# Sch_Fuente.net
KiCad netlist of a schematic drawn in Altium Designer
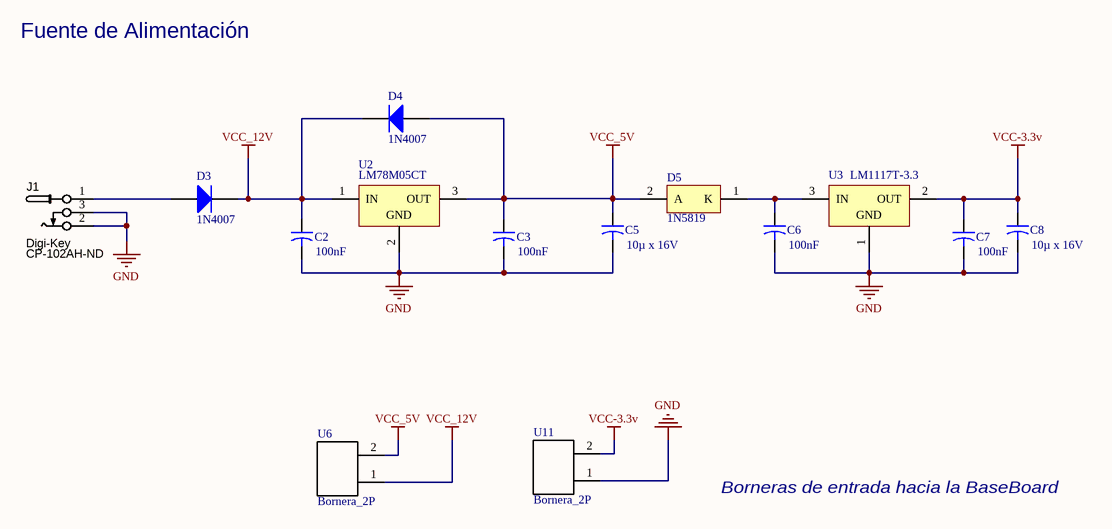
[diagram p0: Sch_Fuente.SchDoc]

(export (version "E")
  (design (tool "Eeschema 10.0.6"))
  (components
    (comp (ref "C2")
      (value "100nF")
      (footprint "CAPR5-4X5")
      (description "Capacitor")
      (fields (field (name "Comment") "Cap2") (field (name "PUBLISHER") "Altium Limited"))
      (libsource (lib "Miscellaneous Devices") (part "Cap2"))
    )
    (comp (ref "C3")
      (value "100nF")
      (footprint "CAPR5-4X5")
      (description "Capacitor")
      (fields (field (name "Comment") "Cap2") (field (name "PUBLISHER") "Altium Limited"))
      (libsource (lib "Miscellaneous Devices") (part "Cap2"))
    )
    (comp (ref "C5")
      (value "10µ x 16V")
      (footprint "CAPR5-4X5")
      (description "Capacitor")
      (fields (field (name "Comment") "Cap2") (field (name "PUBLISHER") "Altium Limited"))
      (libsource (lib "Miscellaneous Devices") (part "Cap2"))
    )
    (comp (ref "C6")
      (value "100nF")
      (footprint "CAPR5-4X5")
      (description "Capacitor")
      (fields (field (name "Comment") "Cap2") (field (name "PUBLISHER") "Altium Limited"))
      (libsource (lib "Miscellaneous Devices") (part "Cap2"))
    )
    (comp (ref "C7")
      (value "100nF")
      (footprint "CAPR5-4X5")
      (description "Capacitor")
      (fields (field (name "Comment") "Cap2") (field (name "PUBLISHER") "Altium Limited"))
      (libsource (lib "Miscellaneous Devices") (part "Cap2"))
    )
    (comp (ref "C8")
      (value "10µ x 16V")
      (footprint "CAPR5-4X5")
      (description "Capacitor")
      (fields (field (name "Comment") "Cap2") (field (name "PUBLISHER") "Altium Limited"))
      (libsource (lib "Miscellaneous Devices") (part "Cap2"))
    )
    (comp (ref "D3")
      (value "1N4007")
      (footprint "DO-41")
      (description "1 Amp General Purpose Rectifier")
      (fields (field (name "PUBLISHER") "Altium Limited"))
      (libsource (lib "Miscellaneous Devices") (part "Diode 1N4007"))
    )
    (comp (ref "D4")
      (value "1N4007")
      (footprint "DO-41")
      (description "1 Amp General Purpose Rectifier")
      (fields (field (name "PUBLISHER") "Altium Limited"))
      (libsource (lib "Miscellaneous Devices") (part "Diode 1N4007"))
    )
    (comp (ref "D5")
      (value "1N5819")
      (footprint "ONSC-AXIAL_LEAD-2-59-10_P")
      (description "Rectifier, 2-Pin Axial_Lead, Pb-Free, Bulk Bag")
      (fields (field (name "MANUFACTURER") "On Semiconductor"))
      (libsource (lib "Altium Content Vault") (part "ONSC-D-K1A2-2_A"))
    )
    (comp (ref "J1")
      (value "CONN_PWR_JACK_2.1x5.5mm")
      (footprint "CONN_PWR_JACK_2.1x5.5mm")
      (description "Power Connector, THT, 2.1mm ID, 5.5mm OD")
      (fields (field (name "SUPPLIER 1") "Digi-Key") (field (name "SUPPLIER PART NUMBER 1") "CP-102AH-ND"))
      (libsource (lib "PBL - Connectors") (part "CONN_PWR_JACK_2.1x5.5mm"))
    )
    (comp (ref "U2")
      (value "LM78M05CT")
      (footprint "T03B")
      (description "3-Terminal Positive Voltage Regulators, 3-pin TO-220")
      (fields (field (name "MANUFACTURER") "National Semiconductor"))
      (libsource (lib "Altium Content Vault") (part "PM-REG-LM2940-SIL3"))
    )
    (comp (ref "U3")
      (value "LM1117T-3.3")
      (footprint "T03B")
      (description "800mA Low-Dropout Linear Regulator, 3-pin TO-220")
      (fields (field (name "MANUFACTURER") "National Semiconductor"))
      (libsource (lib "Altium Content Vault") (part "PM-REG-LM1086-SIL3"))
    )
    (comp (ref "U6")
      (value "Bornera_2P")
      (footprint "Bornera")
      (libsource (lib "Ampli_Lib_Sch") (part "Bornera_2P"))
    )
    (comp (ref "U11")
      (value "Bornera_2P")
      (footprint "Bornera")
      (libsource (lib "Ampli_Lib_Sch") (part "Bornera_2P"))
    )
  )
  (nets
    (net (code "1") (name "GND") (class "Default")
      (node (ref "C2") (pin "2") (pinfunction "2_2") (pintype "passive"))
      (node (ref "C3") (pin "2") (pinfunction "2_2") (pintype "passive"))
      (node (ref "C5") (pin "2") (pinfunction "2_2") (pintype "passive"))
      (node (ref "C6") (pin "2") (pinfunction "2_2") (pintype "passive"))
      (node (ref "C7") (pin "2") (pinfunction "2_2") (pintype "passive"))
      (node (ref "C8") (pin "2") (pinfunction "2_2") (pintype "passive"))
      (node (ref "J1") (pin "2") (pinfunction "2_2") (pintype "passive"))
      (node (ref "J1") (pin "3") (pinfunction "3_3") (pintype "passive"))
      (node (ref "U11") (pin "1") (pinfunction "1_1") (pintype "passive"))
      (node (ref "U2") (pin "2") (pinfunction "GND_2") (pintype "power_in"))
      (node (ref "U3") (pin "1") (pinfunction "GND_1") (pintype "power_in"))
    )
    (net (code "2") (name "Net-(D3-A)") (class "Default")
      (node (ref "D3") (pin "1") (pinfunction "A_1") (pintype "passive"))
      (node (ref "J1") (pin "1") (pinfunction "1_1") (pintype "passive"))
    )
    (net (code "3") (name "Net-(D5-K)") (class "Default")
      (node (ref "C6") (pin "1") (pinfunction "1_1") (pintype "passive"))
      (node (ref "D5") (pin "1") (pinfunction "K_1") (pintype "passive"))
      (node (ref "U3") (pin "3") (pinfunction "IN_3") (pintype "power_in"))
    )
    (net (code "4") (name "VCC-3.3v") (class "Default")
      (node (ref "C7") (pin "1") (pinfunction "1_1") (pintype "passive"))
      (node (ref "C8") (pin "1") (pinfunction "1_1") (pintype "passive"))
      (node (ref "U11") (pin "2") (pinfunction "2_2") (pintype "passive"))
      (node (ref "U3") (pin "2") (pinfunction "OUT_2") (pintype "power_in"))
    )
    (net (code "5") (name "VCC_5V") (class "Default")
      (node (ref "C3") (pin "1") (pinfunction "1_1") (pintype "passive"))
      (node (ref "C5") (pin "1") (pinfunction "1_1") (pintype "passive"))
      (node (ref "D4") (pin "1") (pinfunction "A_1") (pintype "passive"))
      (node (ref "D5") (pin "2") (pinfunction "A_2") (pintype "passive"))
      (node (ref "U2") (pin "3") (pinfunction "OUT_3") (pintype "power_in"))
      (node (ref "U6") (pin "2") (pinfunction "2_2") (pintype "passive"))
    )
    (net (code "6") (name "VCC_12V") (class "Default")
      (node (ref "C2") (pin "1") (pinfunction "1_1") (pintype "passive"))
      (node (ref "D3") (pin "2") (pinfunction "K_2") (pintype "passive"))
      (node (ref "D4") (pin "2") (pinfunction "K_2") (pintype "passive"))
      (node (ref "U2") (pin "1") (pinfunction "IN_1") (pintype "power_in"))
      (node (ref "U6") (pin "1") (pinfunction "1_1") (pintype "passive"))
    )
  )
)
